# BigBoardVERSION2_2layer.net
KiCad netlist of a schematic drawn in Altium Designer
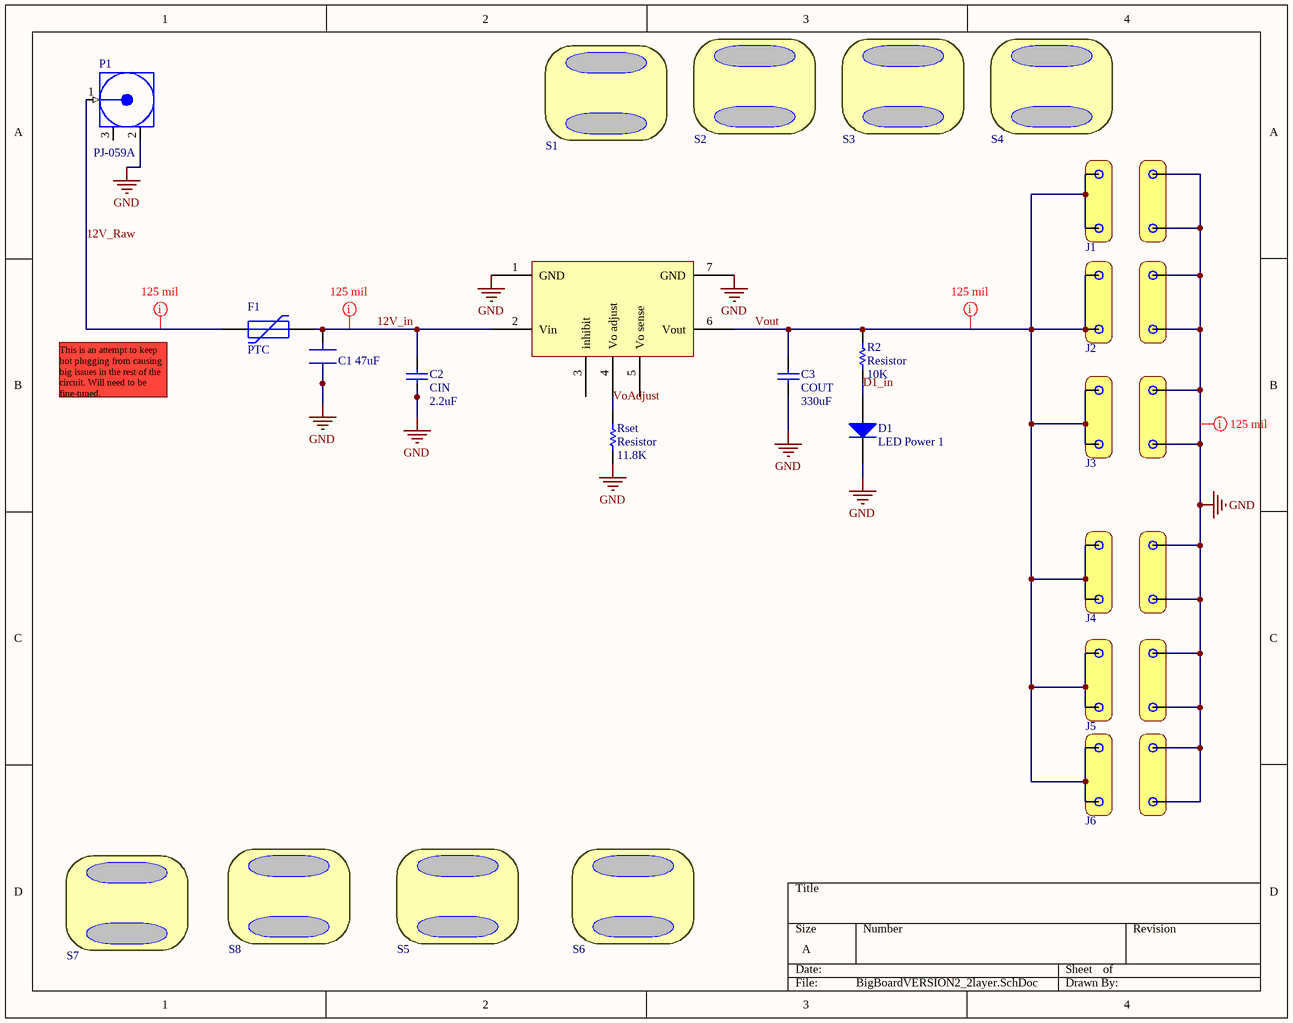
[diagram p0: BigBoardVERSION2_2layer.SchDoc]

(export (version "E")
  (design (tool "Eeschema 10.0.6"))
  (components
    (comp (ref "C1 47uF")
      (value "CapTant6032-28")
      (footprint "CapTant6032-28")
      (description "Polarized Tantalum Capacitor for use in Toaster Charger")
      (libsource (lib "mrsl") (part "CapTant6032-28"))
    )
    (comp (ref "C2")
      (value "CIN")
      (footprint "CAPC2012L")
      (description "Capacitor")
      (fields (field (name "ALTIUM_VALUE") "2.2uF") (field (name "PUBLISHER") "Altium Limited"))
      (libsource (lib "mrsl") (part "Cap"))
    )
    (comp (ref "C3")
      (value "COUT")
      (footprint "RAD-0.2 - POLARIZED")
      (description "Capacitor")
      (fields (field (name "ALTIUM_VALUE") "330uF") (field (name "PUBLISHER") "Altium Limited"))
      (libsource (lib "mrsl") (part "Cap"))
    )
    (comp (ref "D1")
      (value "LED Power 1")
      (footprint "DIODE-0.1")
      (description "Default Diode")
      (fields (field (name "PUBLISHER") "Altium Limited"))
      (libsource (lib "mrsl") (part "Diode"))
    )
    (comp (ref "DCDC1")
      (value "PTN78020WAH")
      (footprint "PTN78020WAH")
      (description "T.I. DC-DC Converter")
      (libsource (lib "mrsl") (part "PTN78020WAH"))
    )
    (comp (ref "F1")
      (value "PTC")
      (footprint "J1-1812")
      (description "Fuse")
      (fields (field (name "PUBLISHER") "Altium Limited"))
      (libsource (lib "mrone") (part "PTC_FUSE"))
    )
    (comp (ref "J1")
      (value "ToasterChargerProng")
      (footprint "ToasterChargerProng")
      (description "Charger Prong Footprint for Toaster Charger")
      (fields (field (name "PUBLISHER") "Altium Limited"))
      (libsource (lib "mrsl") (part "ToasterChargerProng"))
    )
    (comp (ref "J2")
      (value "ToasterChargerProng")
      (footprint "ToasterChargerProng")
      (description "Charger Prong Footprint for Toaster Charger")
      (fields (field (name "PUBLISHER") "Altium Limited"))
      (libsource (lib "mrsl") (part "ToasterChargerProng"))
    )
    (comp (ref "J3")
      (value "ToasterChargerProng")
      (footprint "ToasterChargerProng")
      (description "Charger Prong Footprint for Toaster Charger")
      (fields (field (name "PUBLISHER") "Altium Limited"))
      (libsource (lib "mrsl") (part "ToasterChargerProng"))
    )
    (comp (ref "J4")
      (value "ToasterChargerProng")
      (footprint "ToasterChargerProng")
      (description "Charger Prong Footprint for Toaster Charger")
      (fields (field (name "PUBLISHER") "Altium Limited"))
      (libsource (lib "mrsl") (part "ToasterChargerProng"))
    )
    (comp (ref "J5")
      (value "ToasterChargerProng")
      (footprint "ToasterChargerProng")
      (description "Charger Prong Footprint for Toaster Charger")
      (fields (field (name "PUBLISHER") "Altium Limited"))
      (libsource (lib "mrsl") (part "ToasterChargerProng"))
    )
    (comp (ref "J6")
      (value "ToasterChargerProng")
      (footprint "ToasterChargerProng")
      (description "Charger Prong Footprint for Toaster Charger")
      (fields (field (name "PUBLISHER") "Altium Limited"))
      (libsource (lib "mrsl") (part "ToasterChargerProng"))
    )
    (comp (ref "P1") (value "PJ-059A") (footprint "PJ-059A") (libsource (lib "mrsl") (part "PJ-059A")))
    (comp (ref "R2")
      (value "Resistor")
      (footprint "J1-0603")
      (fields (field (name "ALTIUM_VALUE") "10K") (field (name "PUBLISHER") "Altium Limited"))
      (libsource (lib "mrone") (part "Resistor"))
    )
    (comp (ref "Rset")
      (value "Resistor")
      (footprint "J1-0603")
      (fields (field (name "ALTIUM_VALUE") "11.8K") (field (name "PUBLISHER") "Altium Limited"))
      (libsource (lib "mrone") (part "Resistor"))
    )
    (comp (ref "S1")
      (value "ToasterChargerZiptie")
      (footprint "TOASTERCHARGERZIPTIEREVISED2")
      (description "Slot for Ziptie connection between PCB and Toaster Charger")
      (libsource (lib "mrsl") (part "ToasterChargerZiptie"))
    )
    (comp (ref "S2")
      (value "ToasterChargerZiptie")
      (footprint "TOASTERCHARGERZIPTIEREVISED2")
      (description "Slot for Ziptie connection between PCB and Toaster Charger")
      (libsource (lib "mrsl") (part "ToasterChargerZiptie"))
    )
    (comp (ref "S3")
      (value "ToasterChargerZiptie")
      (footprint "TOASTERCHARGERZIPTIEREVISED2")
      (description "Slot for Ziptie connection between PCB and Toaster Charger")
      (libsource (lib "mrsl") (part "ToasterChargerZiptie"))
    )
    (comp (ref "S4")
      (value "ToasterChargerZiptie")
      (footprint "TOASTERCHARGERZIPTIEREVISED2")
      (description "Slot for Ziptie connection between PCB and Toaster Charger")
      (libsource (lib "mrsl") (part "ToasterChargerZiptie"))
    )
    (comp (ref "S5")
      (value "ToasterChargerZiptie")
      (footprint "TOASTERCHARGERZIPTIEREVISED2")
      (description "Slot for Ziptie connection between PCB and Toaster Charger")
      (libsource (lib "mrsl") (part "ToasterChargerZiptie"))
    )
    (comp (ref "S6")
      (value "ToasterChargerZiptie")
      (footprint "TOASTERCHARGERZIPTIEREVISED2")
      (description "Slot for Ziptie connection between PCB and Toaster Charger")
      (libsource (lib "mrsl") (part "ToasterChargerZiptie"))
    )
    (comp (ref "S7")
      (value "ToasterChargerZiptie")
      (footprint "TOASTERCHARGERZIPTIEREVISED2")
      (description "Slot for Ziptie connection between PCB and Toaster Charger")
      (libsource (lib "mrsl") (part "ToasterChargerZiptie"))
    )
    (comp (ref "S8")
      (value "ToasterChargerZiptie")
      (footprint "TOASTERCHARGERZIPTIEREVISED2")
      (description "Slot for Ziptie connection between PCB and Toaster Charger")
      (libsource (lib "mrsl") (part "ToasterChargerZiptie"))
    )
  )
  (nets
    (net (code "1") (name "/12V_Raw") (class "Default")
      (node (ref "F1") (pin "1") (pinfunction "1_1") (pintype "passive"))
      (node (ref "P1") (pin "1") (pinfunction "VCC_1") (pintype "input"))
    )
    (net (code "2") (name "/12V_in") (class "Default")
      (node (ref "C1 47uF") (pin "1") (pintype "passive"))
      (node (ref "C2") (pin "2") (pinfunction "2_2") (pintype "passive"))
      (node (ref "DCDC1") (pin "2") (pinfunction "Vin_2") (pintype "passive"))
      (node (ref "F1") (pin "2") (pinfunction "2_2") (pintype "passive"))
    )
    (net (code "3") (name "/D1_in") (class "Default")
      (node (ref "D1") (pin "1") (pinfunction "A_1") (pintype "passive"))
      (node (ref "R2") (pin "2") (pinfunction "2_2") (pintype "passive"))
    )
    (net (code "4") (name "/VoAdjust") (class "Default")
      (node (ref "DCDC1") (pin "4") (pinfunction "Vo_adjust_4") (pintype "passive"))
      (node (ref "Rset") (pin "1") (pinfunction "1_1") (pintype "passive"))
    )
    (net (code "5") (name "/Vout") (class "Default")
      (node (ref "C3") (pin "2") (pinfunction "2_2") (pintype "passive"))
      (node (ref "DCDC1") (pin "6") (pinfunction "Vout_6") (pintype "passive"))
      (node (ref "J1") (pin "1") (pinfunction "1_1") (pintype "passive"))
      (node (ref "J1") (pin "2") (pinfunction "2_2") (pintype "passive"))
      (node (ref "J2") (pin "1") (pinfunction "1_1") (pintype "passive"))
      (node (ref "J2") (pin "2") (pinfunction "2_2") (pintype "passive"))
      (node (ref "J3") (pin "1") (pinfunction "1_1") (pintype "passive"))
      (node (ref "J3") (pin "2") (pinfunction "2_2") (pintype "passive"))
      (node (ref "J4") (pin "1") (pinfunction "1_1") (pintype "passive"))
      (node (ref "J4") (pin "2") (pinfunction "2_2") (pintype "passive"))
      (node (ref "J5") (pin "1") (pinfunction "1_1") (pintype "passive"))
      (node (ref "J5") (pin "2") (pinfunction "2_2") (pintype "passive"))
      (node (ref "J6") (pin "1") (pinfunction "1_1") (pintype "passive"))
      (node (ref "J6") (pin "2") (pinfunction "2_2") (pintype "passive"))
      (node (ref "R2") (pin "1") (pinfunction "1_1") (pintype "passive"))
    )
    (net (code "6") (name "GND") (class "Default")
      (node (ref "C1 47uF") (pin "2") (pintype "passive"))
      (node (ref "C2") (pin "1") (pinfunction "1_1") (pintype "passive"))
      (node (ref "C3") (pin "1") (pinfunction "1_1") (pintype "passive"))
      (node (ref "D1") (pin "2") (pinfunction "K_2") (pintype "passive"))
      (node (ref "DCDC1") (pin "1") (pinfunction "GND_1") (pintype "passive"))
      (node (ref "DCDC1") (pin "7") (pinfunction "GND_7") (pintype "passive"))
      (node (ref "J1") (pin "3") (pinfunction "3_3") (pintype "passive"))
      (node (ref "J1") (pin "4") (pinfunction "4_4") (pintype "passive"))
      (node (ref "J2") (pin "3") (pinfunction "3_3") (pintype "passive"))
      (node (ref "J2") (pin "4") (pinfunction "4_4") (pintype "passive"))
      (node (ref "J3") (pin "3") (pinfunction "3_3") (pintype "passive"))
      (node (ref "J3") (pin "4") (pinfunction "4_4") (pintype "passive"))
      (node (ref "J4") (pin "3") (pinfunction "3_3") (pintype "passive"))
      (node (ref "J4") (pin "4") (pinfunction "4_4") (pintype "passive"))
      (node (ref "J5") (pin "3") (pinfunction "3_3") (pintype "passive"))
      (node (ref "J5") (pin "4") (pinfunction "4_4") (pintype "passive"))
      (node (ref "J6") (pin "3") (pinfunction "3_3") (pintype "passive"))
      (node (ref "J6") (pin "4") (pinfunction "4_4") (pintype "passive"))
      (node (ref "P1") (pin "2") (pinfunction "GND_2") (pintype "power_in"))
      (node (ref "Rset") (pin "2") (pinfunction "2_2") (pintype "passive"))
    )
    (net (code "7") (name "unconnected-(DCDC1-Vo_sense-Pad5)") (class "Default")
      (node (ref "DCDC1") (pin "5") (pinfunction "Vo_sense_5") (pintype "passive"))
    )
    (net (code "8") (name "unconnected-(DCDC1-inhibit-Pad3)") (class "Default")
      (node (ref "DCDC1") (pin "3") (pinfunction "inhibit_3") (pintype "passive"))
    )
    (net (code "9") (name "unconnected-(P1-Pad3)") (class "Default")
      (node (ref "P1") (pin "3") (pintype "passive"))
    )
  )
)
